# Indication.net
KiCad netlist of a schematic drawn in Altium Designer
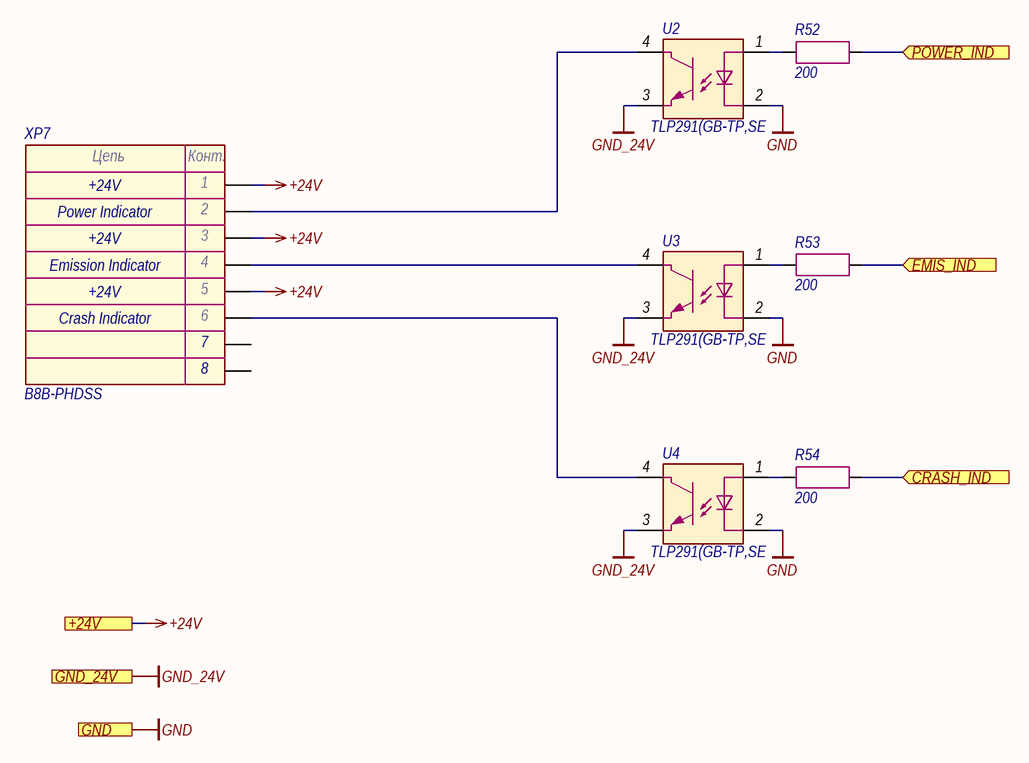
[diagram p0: Indication.SchDoc]

(export (version "E")
  (design (tool "Eeschema 10.0.6"))
  (components
    (comp (ref "R52")
      (value "200")
      (footprint "Pcb_library:RES_0603")
      (fields (field (name "MANUFACTURER") "Yageo"))
      (libsource (lib "Schem_library") (part "Resistor"))
    )
    (comp (ref "R53")
      (value "200")
      (footprint "Pcb_library:RES_0603")
      (fields (field (name "MANUFACTURER") "Yageo"))
      (libsource (lib "Schem_library") (part "Resistor"))
    )
    (comp (ref "R54")
      (value "200")
      (footprint "Pcb_library:RES_0603")
      (fields (field (name "MANUFACTURER") "Yageo"))
      (libsource (lib "Schem_library") (part "Resistor"))
    )
    (comp (ref "U2")
      (value "TLP291(GB-TP,SE")
      (footprint "Pcb_library:11-3C1")
      (fields (field (name "MANUFACTURER") "Toshiba"))
      (libsource (lib "Schem_library") (part "TLP291"))
    )
    (comp (ref "U3")
      (value "TLP291(GB-TP,SE")
      (footprint "Pcb_library:11-3C1")
      (fields (field (name "MANUFACTURER") "Toshiba"))
      (libsource (lib "Schem_library") (part "TLP291"))
    )
    (comp (ref "U4")
      (value "TLP291(GB-TP,SE")
      (footprint "Pcb_library:11-3C1")
      (fields (field (name "MANUFACTURER") "Toshiba"))
      (libsource (lib "Schem_library") (part "TLP291"))
    )
    (comp (ref "XP7")
      (value "B8B-PHDSS")
      (footprint "Pcb_library:B8B-PHDSS")
      (fields (field (name "MANUFACTURER") "JST"))
      (libsource (lib "Schem_library") (part "Connector-8"))
    )
  )
  (nets
    (net (code "1") (name "+24V") (class "Default")
      (node (ref "XP7") (pin "1") (pintype "passive"))
      (node (ref "XP7") (pin "3") (pintype "passive"))
      (node (ref "XP7") (pin "5") (pintype "passive"))
    )
    (net (code "2") (name "/CRASH_IND") (class "Default")
      (node (ref "R54") (pin "2") (pinfunction "2_2") (pintype "passive"))
    )
    (net (code "3") (name "/EMIS_IND") (class "Default")
      (node (ref "R53") (pin "2") (pinfunction "2_2") (pintype "passive"))
    )
    (net (code "4") (name "/POWER_IND") (class "Default")
      (node (ref "R52") (pin "2") (pinfunction "2_2") (pintype "passive"))
    )
    (net (code "5") (name "GND") (class "Default")
      (node (ref "U2") (pin "2") (pintype "passive"))
      (node (ref "U3") (pin "2") (pintype "passive"))
      (node (ref "U4") (pin "2") (pintype "passive"))
    )
    (net (code "6") (name "GND_24V") (class "Default")
      (node (ref "U2") (pin "3") (pintype "passive"))
      (node (ref "U3") (pin "3") (pintype "passive"))
      (node (ref "U4") (pin "3") (pintype "passive"))
    )
    (net (code "7") (name "Net-(R52-Pad1)") (class "Default")
      (node (ref "R52") (pin "1") (pinfunction "1_1") (pintype "passive"))
      (node (ref "U2") (pin "1") (pintype "passive"))
    )
    (net (code "8") (name "Net-(R53-Pad1)") (class "Default")
      (node (ref "R53") (pin "1") (pinfunction "1_1") (pintype "passive"))
      (node (ref "U3") (pin "1") (pintype "passive"))
    )
    (net (code "9") (name "Net-(R54-Pad1)") (class "Default")
      (node (ref "R54") (pin "1") (pinfunction "1_1") (pintype "passive"))
      (node (ref "U4") (pin "1") (pintype "passive"))
    )
    (net (code "10") (name "Net-(U2-Pad4)") (class "Default")
      (node (ref "U2") (pin "4") (pintype "passive"))
      (node (ref "XP7") (pin "2") (pintype "passive"))
    )
    (net (code "11") (name "Net-(U3-Pad4)") (class "Default")
      (node (ref "U3") (pin "4") (pintype "passive"))
      (node (ref "XP7") (pin "4") (pintype "passive"))
    )
    (net (code "12") (name "Net-(U4-Pad4)") (class "Default")
      (node (ref "U4") (pin "4") (pintype "passive"))
      (node (ref "XP7") (pin "6") (pintype "passive"))
    )
    (net (code "13") (name "unconnected-(XP7-Pad7)") (class "Default")
      (node (ref "XP7") (pin "7") (pintype "passive"))
    )
    (net (code "14") (name "unconnected-(XP7-Pad8)") (class "Default")
      (node (ref "XP7") (pin "8") (pintype "passive"))
    )
  )
)
